# Master.net
KiCad netlist of a schematic drawn in Altium Designer
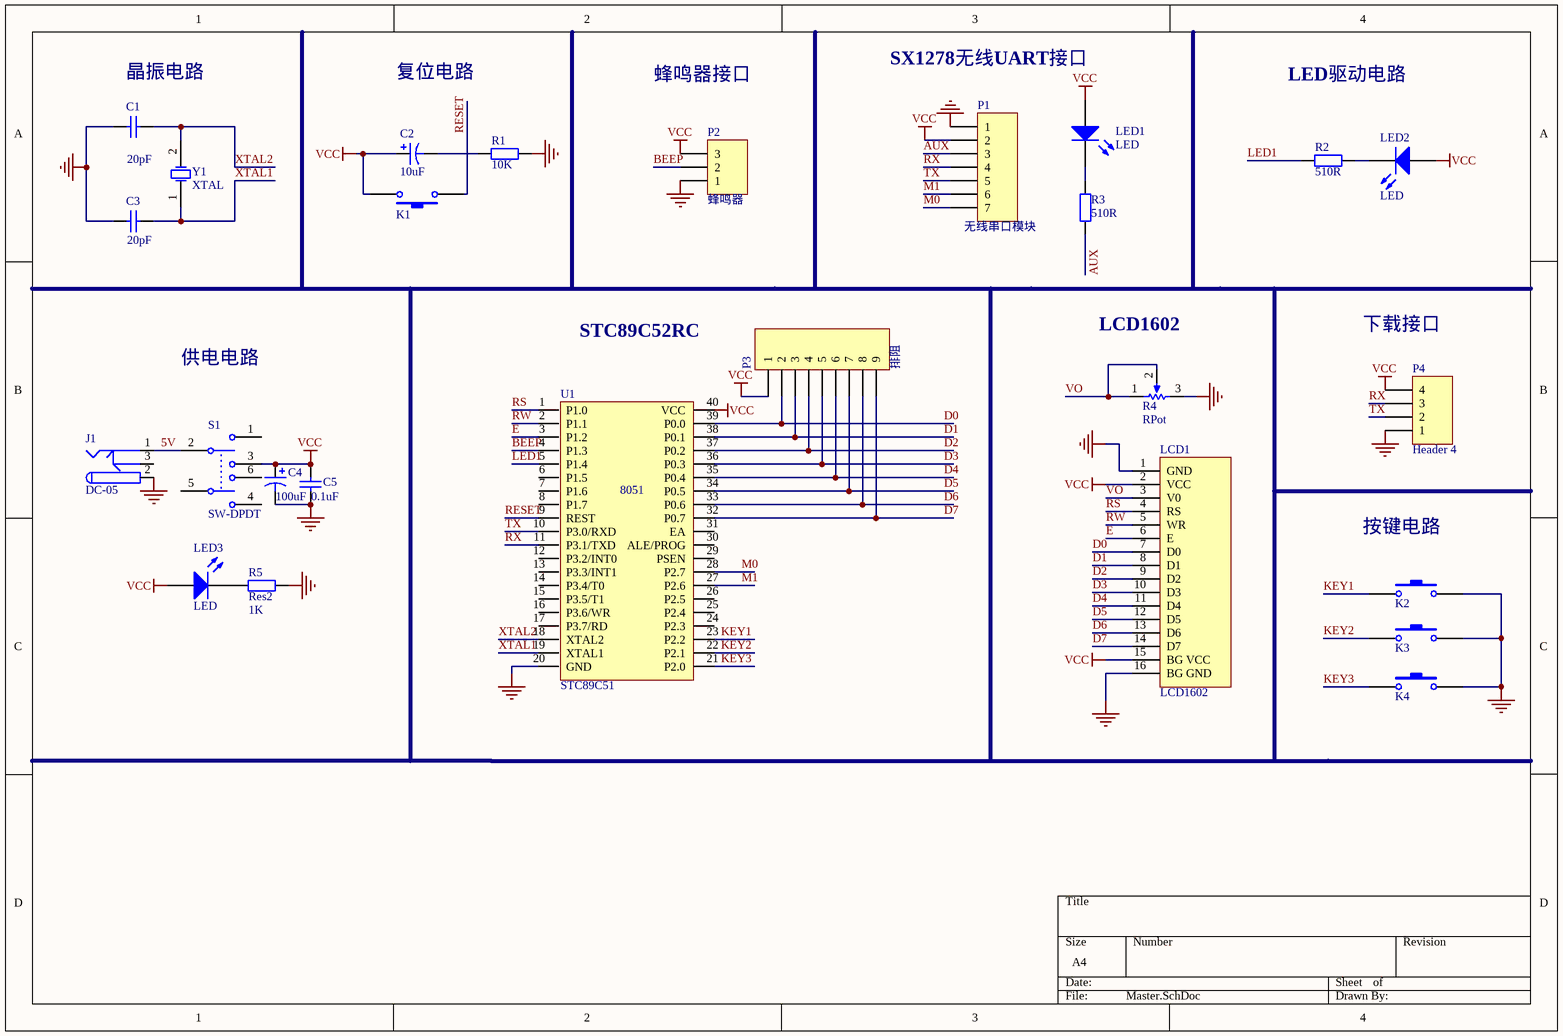
[diagram p0: Master.SchDoc]

(export (version "E")
  (design (tool "Eeschema 10.0.6"))
  (components
    (comp (ref "C1")
      (value "20pF")
      (footprint "RAD-0.1")
      (description "Capacitor")
      (fields (field (name "Comment") "Cap") (field (name "PUBLISHER") "Altium Limited"))
      (libsource (lib "Miscellaneous Devices") (part "Cap"))
    )
    (comp (ref "C2")
      (value "10uF")
      (footprint "RB.1/.2")
      (description "Polarized Capacitor (Radial)")
      (fields (field (name "Comment") "Cap Pol1") (field (name "PUBLISHER") "Altium Limited"))
      (libsource (lib "Miscellaneous Devices") (part "Cap Pol1"))
    )
    (comp (ref "C3")
      (value "20pF")
      (footprint "RAD-0.1")
      (description "Capacitor")
      (fields (field (name "Comment") "Cap") (field (name "PUBLISHER") "Altium Limited"))
      (libsource (lib "Miscellaneous Devices") (part "Cap"))
    )
    (comp (ref "C4")
      (value "100uF")
      (footprint "RB.1/.2")
      (description "Polarized Capacitor (Radial)")
      (fields (field (name "Comment") "Cap Pol1") (field (name "PUBLISHER") "Altium Limited"))
      (libsource (lib "Miscellaneous Devices") (part "Cap Pol1"))
    )
    (comp (ref "C5")
      (value "0.1uF")
      (footprint "RAD-0.1")
      (description "Capacitor")
      (fields (field (name "Comment") "Cap") (field (name "PUBLISHER") "Altium Limited"))
      (libsource (lib "Miscellaneous Devices") (part "Cap"))
    )
    (comp (ref "J1") (value "DC-05") (footprint "DC-05") (libsource (lib "My library") (part "DC-05")))
    (comp (ref "K1") (value "四脚按键") (footprint "四脚按键") (libsource (lib "My library") (part "四脚按键")))
    (comp (ref "K2") (value "四脚按键") (footprint "四脚按键") (libsource (lib "My library") (part "四脚按键")))
    (comp (ref "K3") (value "四脚按键") (footprint "四脚按键") (libsource (lib "My library") (part "四脚按键")))
    (comp (ref "K4") (value "四脚按键") (footprint "四脚按键") (libsource (lib "My library") (part "四脚按键")))
    (comp (ref "LCD1")
      (value "LCD1602")
      (footprint "LCD1602")
      (libsource (lib "My library") (part "LCD1602"))
    )
    (comp (ref "LED1") (value "LED") (footprint "LED") (libsource (lib "My library") (part "LED")))
    (comp (ref "LED2") (value "LED") (footprint "LED") (libsource (lib "My library") (part "LED")))
    (comp (ref "LED3") (value "LED") (footprint "LED") (libsource (lib "My library") (part "LED")))
    (comp (ref "P1")
      (value "无线串口模块")
      (footprint "AS32-TTL-100")
      (description "Header, 7-Pin")
      (fields (field (name "PUBLISHER") "Altium Limited"))
      (libsource (lib "Miscellaneous Connectors") (part "Header 7"))
    )
    (comp (ref "P2")
      (value "蜂鸣器")
      (footprint "HDR1X3")
      (description "Header, 3-Pin")
      (fields (field (name "PUBLISHER") "Altium Limited"))
      (libsource (lib "Miscellaneous Connectors") (part "Header 3"))
    )
    (comp (ref "P3")
      (value "排阻")
      (footprint "HDR1X9")
      (description "Header, 9-Pin")
      (fields (field (name "PUBLISHER") "Altium Limited"))
      (libsource (lib "Miscellaneous Connectors") (part "Header 9"))
    )
    (comp (ref "P4")
      (value "Header 4")
      (footprint "HDR1X4")
      (description "Header, 4-Pin")
      (fields (field (name "PUBLISHER") "Altium Limited"))
      (libsource (lib "Miscellaneous Connectors") (part "Header 4"))
    )
    (comp (ref "R1")
      (value "10K")
      (footprint "AXIAL-0.4")
      (description "Resistor")
      (fields (field (name "Comment") "Res2") (field (name "PUBLISHER") "Altium Limited"))
      (libsource (lib "Miscellaneous Devices") (part "Res2"))
    )
    (comp (ref "R2")
      (value "510R")
      (footprint "AXIAL-0.4")
      (description "Resistor")
      (fields (field (name "Comment") "Res2") (field (name "PUBLISHER") "Altium Limited"))
      (libsource (lib "") (part "Res2_2"))
    )
    (comp (ref "R3")
      (value "510R")
      (footprint "AXIAL-0.4")
      (description "Resistor")
      (fields (field (name "Comment") "Res2") (field (name "PUBLISHER") "Altium Limited"))
      (libsource (lib "") (part "Res2_1"))
    )
    (comp (ref "R4") (value "RPot") (footprint "RPot") (libsource (lib "My library") (part "RPOT")))
    (comp (ref "R5")
      (value "Res2")
      (footprint "AXIAL-0.4")
      (description "Resistor")
      (fields (field (name "ALTIUM_VALUE") "1K") (field (name "PUBLISHER") "Altium Limited"))
      (libsource (lib "") (part "Res2_2"))
    )
    (comp (ref "S1")
      (value "SW-DPDT")
      (footprint "SWITCH_B1")
      (description "单刀双掷开关")
      (fields (field (name "PUBLISHER") "Altium Limited"))
      (libsource (lib "Fszhang") (part "SW-DPDT"))
    )
    (comp (ref "U1") (value "STC89C51") (footprint "DIP-40") (libsource (lib "My library") (part "STC89C51")))
    (comp (ref "Y1")
      (value "XTAL")
      (footprint "XTAL_US")
      (description "Crystal Oscillator")
      (fields (field (name "PUBLISHER") "Altium Limited"))
      (libsource (lib "Miscellaneous Devices") (part "XTAL"))
    )
  )
  (nets
    (net (code "1") (name "/5V") (class "Default")
      (node (ref "J1") (pin "1") (pinfunction "1_1") (pintype "passive"))
      (node (ref "S1") (pin "2") (pinfunction "2_2") (pintype "passive"))
    )
    (net (code "2") (name "/AUX") (class "Default")
      (node (ref "P1") (pin "3") (pinfunction "3_3") (pintype "passive"))
      (node (ref "R3") (pin "1") (pinfunction "1_1") (pintype "passive"))
    )
    (net (code "3") (name "/BEEP") (class "Default")
      (node (ref "P2") (pin "2") (pinfunction "2_2") (pintype "passive"))
      (node (ref "U1") (pin "4") (pinfunction "P1.3_4") (pintype "passive"))
    )
    (net (code "4") (name "/D0") (class "Default")
      (node (ref "LCD1") (pin "7") (pinfunction "D0_7") (pintype "power_in"))
      (node (ref "P3") (pin "2") (pinfunction "2_2") (pintype "passive"))
      (node (ref "U1") (pin "39") (pinfunction "P0.0_39") (pintype "passive"))
    )
    (net (code "5") (name "/D1") (class "Default")
      (node (ref "LCD1") (pin "8") (pinfunction "D1_8") (pintype "power_in"))
      (node (ref "P3") (pin "3") (pinfunction "3_3") (pintype "passive"))
      (node (ref "U1") (pin "38") (pinfunction "P0.1_38") (pintype "passive"))
    )
    (net (code "6") (name "/D2") (class "Default")
      (node (ref "LCD1") (pin "9") (pinfunction "D2_9") (pintype "power_in"))
      (node (ref "P3") (pin "4") (pinfunction "4_4") (pintype "passive"))
      (node (ref "U1") (pin "37") (pinfunction "P0.2_37") (pintype "passive"))
    )
    (net (code "7") (name "/D3") (class "Default")
      (node (ref "LCD1") (pin "10") (pinfunction "D3_10") (pintype "power_in"))
      (node (ref "P3") (pin "5") (pinfunction "5_5") (pintype "passive"))
      (node (ref "U1") (pin "36") (pinfunction "P0.3_36") (pintype "passive"))
    )
    (net (code "8") (name "/D4") (class "Default")
      (node (ref "LCD1") (pin "11") (pinfunction "D4_11") (pintype "power_in"))
      (node (ref "P3") (pin "6") (pinfunction "6_6") (pintype "passive"))
      (node (ref "U1") (pin "35") (pinfunction "P0.4_35") (pintype "passive"))
    )
    (net (code "9") (name "/D5") (class "Default")
      (node (ref "LCD1") (pin "12") (pinfunction "D5_12") (pintype "power_in"))
      (node (ref "P3") (pin "7") (pinfunction "7_7") (pintype "passive"))
      (node (ref "U1") (pin "34") (pinfunction "P0.5_34") (pintype "passive"))
    )
    (net (code "10") (name "/D6") (class "Default")
      (node (ref "LCD1") (pin "13") (pinfunction "D6_13") (pintype "power_in"))
      (node (ref "P3") (pin "8") (pinfunction "8_8") (pintype "passive"))
      (node (ref "U1") (pin "33") (pinfunction "P0.6_33") (pintype "passive"))
    )
    (net (code "11") (name "/D7") (class "Default")
      (node (ref "LCD1") (pin "14") (pinfunction "D7_14") (pintype "power_in"))
      (node (ref "P3") (pin "9") (pinfunction "9_9") (pintype "passive"))
      (node (ref "U1") (pin "32") (pinfunction "P0.7_32") (pintype "passive"))
    )
    (net (code "12") (name "/E") (class "Default")
      (node (ref "LCD1") (pin "6") (pinfunction "E_6") (pintype "power_in"))
      (node (ref "U1") (pin "3") (pinfunction "P1.2_3") (pintype "passive"))
    )
    (net (code "13") (name "/KEY1") (class "Default")
      (node (ref "K2") (pin "2") (pinfunction "2_2") (pintype "passive"))
      (node (ref "U1") (pin "23") (pinfunction "P2.2_23") (pintype "passive"))
    )
    (net (code "14") (name "/KEY2") (class "Default")
      (node (ref "K3") (pin "2") (pinfunction "2_2") (pintype "passive"))
      (node (ref "U1") (pin "22") (pinfunction "P2.1_22") (pintype "passive"))
    )
    (net (code "15") (name "/KEY3") (class "Default")
      (node (ref "K4") (pin "2") (pinfunction "2_2") (pintype "passive"))
      (node (ref "U1") (pin "21") (pinfunction "P2.0_21") (pintype "passive"))
    )
    (net (code "16") (name "/LED1") (class "Default")
      (node (ref "R2") (pin "1") (pinfunction "1_1") (pintype "passive"))
      (node (ref "U1") (pin "5") (pinfunction "P1.4_5") (pintype "passive"))
    )
    (net (code "17") (name "/M0") (class "Default")
      (node (ref "P1") (pin "7") (pinfunction "7_7") (pintype "passive"))
      (node (ref "U1") (pin "28") (pinfunction "P2.7_28") (pintype "passive"))
    )
    (net (code "18") (name "/M1") (class "Default")
      (node (ref "P1") (pin "6") (pinfunction "6_6") (pintype "passive"))
      (node (ref "U1") (pin "27") (pinfunction "P2.6_27") (pintype "passive"))
    )
    (net (code "19") (name "/RESET") (class "Default")
      (node (ref "K1") (pin "2") (pinfunction "2_2") (pintype "passive"))
      (node (ref "U1") (pin "9") (pinfunction "REST_9") (pintype "passive"))
    )
    (net (code "20") (name "/RS") (class "Default")
      (node (ref "LCD1") (pin "4") (pinfunction "RS_4") (pintype "power_in"))
      (node (ref "U1") (pin "1") (pinfunction "P1.0_1") (pintype "passive"))
    )
    (net (code "21") (name "/RW") (class "Default")
      (node (ref "LCD1") (pin "5") (pinfunction "WR_5") (pintype "power_in"))
      (node (ref "U1") (pin "2") (pinfunction "P1.1_2") (pintype "passive"))
    )
    (net (code "22") (name "/RX") (class "Default")
      (node (ref "P1") (pin "4") (pinfunction "4_4") (pintype "passive"))
      (node (ref "P4") (pin "3") (pinfunction "3_3") (pintype "passive"))
      (node (ref "U1") (pin "11") (pinfunction "P3.1/TXD_11") (pintype "passive"))
    )
    (net (code "23") (name "/TX") (class "Default")
      (node (ref "P1") (pin "5") (pinfunction "5_5") (pintype "passive"))
      (node (ref "P4") (pin "2") (pinfunction "2_2") (pintype "passive"))
      (node (ref "U1") (pin "10") (pinfunction "P3.0/RXD_10") (pintype "passive"))
    )
    (net (code "24") (name "/VO") (class "Default")
      (node (ref "LCD1") (pin "3") (pinfunction "V0_3") (pintype "power_in"))
      (node (ref "R4") (pin "1") (pinfunction "1_1") (pintype "passive"))
      (node (ref "R4") (pin "2") (pinfunction "2_2") (pintype "passive"))
    )
    (net (code "25") (name "/XTAL1") (class "Default")
      (node (ref "C3") (pin "1") (pinfunction "1_1") (pintype "passive"))
      (node (ref "U1") (pin "19") (pinfunction "XTAL1_19") (pintype "passive"))
      (node (ref "Y1") (pin "1") (pinfunction "OSC1_1") (pintype "passive"))
    )
    (net (code "26") (name "/XTAL2") (class "Default")
      (node (ref "C1") (pin "1") (pinfunction "1_1") (pintype "passive"))
      (node (ref "U1") (pin "18") (pinfunction "XTAL2_18") (pintype "passive"))
      (node (ref "Y1") (pin "2") (pinfunction "OSC2_2") (pintype "passive"))
    )
    (net (code "27") (name "GND") (class "Default")
      (node (ref "C1") (pin "2") (pinfunction "2_2") (pintype "passive"))
      (node (ref "C3") (pin "2") (pinfunction "2_2") (pintype "passive"))
      (node (ref "C4") (pin "2") (pinfunction "2_2") (pintype "passive"))
      (node (ref "C5") (pin "1") (pinfunction "1_1") (pintype "passive"))
      (node (ref "J1") (pin "2") (pinfunction "2_2") (pintype "passive"))
      (node (ref "K2") (pin "1") (pinfunction "1_1") (pintype "passive"))
      (node (ref "K3") (pin "1") (pinfunction "1_1") (pintype "passive"))
      (node (ref "K4") (pin "1") (pinfunction "1_1") (pintype "passive"))
      (node (ref "LCD1") (pin "1") (pinfunction "GND_1") (pintype "power_in"))
      (node (ref "LCD1") (pin "16") (pinfunction "BG_GND_16") (pintype "power_in"))
      (node (ref "P1") (pin "1") (pinfunction "1_1") (pintype "passive"))
      (node (ref "P2") (pin "1") (pinfunction "1_1") (pintype "passive"))
      (node (ref "P4") (pin "1") (pinfunction "1_1") (pintype "passive"))
      (node (ref "R1") (pin "1") (pinfunction "1_1") (pintype "passive"))
      (node (ref "R4") (pin "3") (pinfunction "3_3") (pintype "passive"))
      (node (ref "R5") (pin "2") (pinfunction "2_2") (pintype "passive"))
      (node (ref "U1") (pin "20") (pinfunction "GND_20") (pintype "passive"))
    )
    (net (code "28") (name "Net-(C2-Pad2)") (class "Default")
      (node (ref "C2") (pin "2") (pinfunction "2_2") (pintype "passive"))
      (node (ref "R1") (pin "2") (pinfunction "2_2") (pintype "passive"))
    )
    (net (code "29") (name "Net-(LED1-Pad2)") (class "Default")
      (node (ref "LED1") (pin "2") (pinfunction "2_2") (pintype "passive"))
      (node (ref "R3") (pin "2") (pinfunction "2_2") (pintype "passive"))
    )
    (net (code "30") (name "Net-(LED2-Pad2)") (class "Default")
      (node (ref "LED2") (pin "2") (pinfunction "2_2") (pintype "passive"))
      (node (ref "R2") (pin "2") (pinfunction "2_2") (pintype "passive"))
    )
    (net (code "31") (name "Net-(LED3-Pad2)") (class "Default")
      (node (ref "LED3") (pin "2") (pinfunction "2_2") (pintype "passive"))
      (node (ref "R5") (pin "1") (pinfunction "1_1") (pintype "passive"))
    )
    (net (code "32") (name "VCC") (class "Default")
      (node (ref "C2") (pin "1") (pinfunction "1_1") (pintype "passive"))
      (node (ref "C4") (pin "1") (pinfunction "1_1") (pintype "passive"))
      (node (ref "C5") (pin "2") (pinfunction "2_2") (pintype "passive"))
      (node (ref "K1") (pin "1") (pinfunction "1_1") (pintype "passive"))
      (node (ref "LCD1") (pin "15") (pinfunction "BG_VCC_15") (pintype "power_in"))
      (node (ref "LCD1") (pin "2") (pinfunction "VCC_2") (pintype "power_in"))
      (node (ref "LED1") (pin "1") (pinfunction "1_1") (pintype "passive"))
      (node (ref "LED2") (pin "1") (pinfunction "1_1") (pintype "passive"))
      (node (ref "LED3") (pin "1") (pinfunction "1_1") (pintype "passive"))
      (node (ref "P1") (pin "2") (pinfunction "2_2") (pintype "passive"))
      (node (ref "P2") (pin "3") (pinfunction "3_3") (pintype "passive"))
      (node (ref "P3") (pin "1") (pinfunction "1_1") (pintype "passive"))
      (node (ref "P4") (pin "4") (pinfunction "4_4") (pintype "passive"))
      (node (ref "S1") (pin "3") (pinfunction "3_3") (pintype "passive"))
      (node (ref "U1") (pin "40") (pinfunction "VCC_40") (pintype "passive"))
    )
    (net (code "33") (name "unconnected-(J1-Pad3)") (class "Default")
      (node (ref "J1") (pin "3") (pinfunction "3_3") (pintype "passive"))
    )
    (net (code "34") (name "unconnected-(S1-Pad1)") (class "Default")
      (node (ref "S1") (pin "1") (pinfunction "1_1") (pintype "passive"))
    )
    (net (code "35") (name "unconnected-(S1-Pad4)") (class "Default")
      (node (ref "S1") (pin "4") (pinfunction "4_4") (pintype "passive"))
    )
    (net (code "36") (name "unconnected-(S1-Pad5)") (class "Default")
      (node (ref "S1") (pin "5") (pinfunction "5_5") (pintype "passive"))
    )
    (net (code "37") (name "unconnected-(S1-Pad6)") (class "Default")
      (node (ref "S1") (pin "6") (pinfunction "6_6") (pintype "passive"))
    )
    (net (code "38") (name "unconnected-(U1-ALE{slash}PROG-Pad30)") (class "Default")
      (node (ref "U1") (pin "30") (pinfunction "ALE/PROG_30") (pintype "passive"))
    )
    (net (code "39") (name "unconnected-(U1-EA-Pad31)") (class "Default")
      (node (ref "U1") (pin "31") (pinfunction "EA_31") (pintype "passive"))
    )
    (net (code "40") (name "unconnected-(U1-P1.5-Pad6)") (class "Default")
      (node (ref "U1") (pin "6") (pinfunction "P1.5_6") (pintype "passive"))
    )
    (net (code "41") (name "unconnected-(U1-P1.6-Pad7)") (class "Default")
      (node (ref "U1") (pin "7") (pinfunction "P1.6_7") (pintype "passive"))
    )
    (net (code "42") (name "unconnected-(U1-P1.7-Pad8)") (class "Default")
      (node (ref "U1") (pin "8") (pinfunction "P1.7_8") (pintype "passive"))
    )
    (net (code "43") (name "unconnected-(U1-P2.3-Pad24)") (class "Default")
      (node (ref "U1") (pin "24") (pinfunction "P2.3_24") (pintype "passive"))
    )
    (net (code "44") (name "unconnected-(U1-P2.4-Pad25)") (class "Default")
      (node (ref "U1") (pin "25") (pinfunction "P2.4_25") (pintype "passive"))
    )
    (net (code "45") (name "unconnected-(U1-P2.5-Pad26)") (class "Default")
      (node (ref "U1") (pin "26") (pinfunction "P2.5_26") (pintype "passive"))
    )
    (net (code "46") (name "unconnected-(U1-P3.2{slash}INT0-Pad12)") (class "Default")
      (node (ref "U1") (pin "12") (pinfunction "P3.2/INT0_12") (pintype "passive"))
    )
    (net (code "47") (name "unconnected-(U1-P3.3{slash}INT1-Pad13)") (class "Default")
      (node (ref "U1") (pin "13") (pinfunction "P3.3/INT1_13") (pintype "passive"))
    )
    (net (code "48") (name "unconnected-(U1-P3.4{slash}T0-Pad14)") (class "Default")
      (node (ref "U1") (pin "14") (pinfunction "P3.4/T0_14") (pintype "passive"))
    )
    (net (code "49") (name "unconnected-(U1-P3.5{slash}T1-Pad15)") (class "Default")
      (node (ref "U1") (pin "15") (pinfunction "P3.5/T1_15") (pintype "passive"))
    )
    (net (code "50") (name "unconnected-(U1-P3.6{slash}WR-Pad16)") (class "Default")
      (node (ref "U1") (pin "16") (pinfunction "P3.6/WR_16") (pintype "passive"))
    )
    (net (code "51") (name "unconnected-(U1-P3.7{slash}RD-Pad17)") (class "Default")
      (node (ref "U1") (pin "17") (pinfunction "P3.7/RD_17") (pintype "passive"))
    )
    (net (code "52") (name "unconnected-(U1-PSEN-Pad29)") (class "Default")
      (node (ref "U1") (pin "29") (pinfunction "PSEN_29") (pintype "passive"))
    )
  )
)
